# C64_Promenade.net
KiCad netlist of a schematic drawn in EAGLE
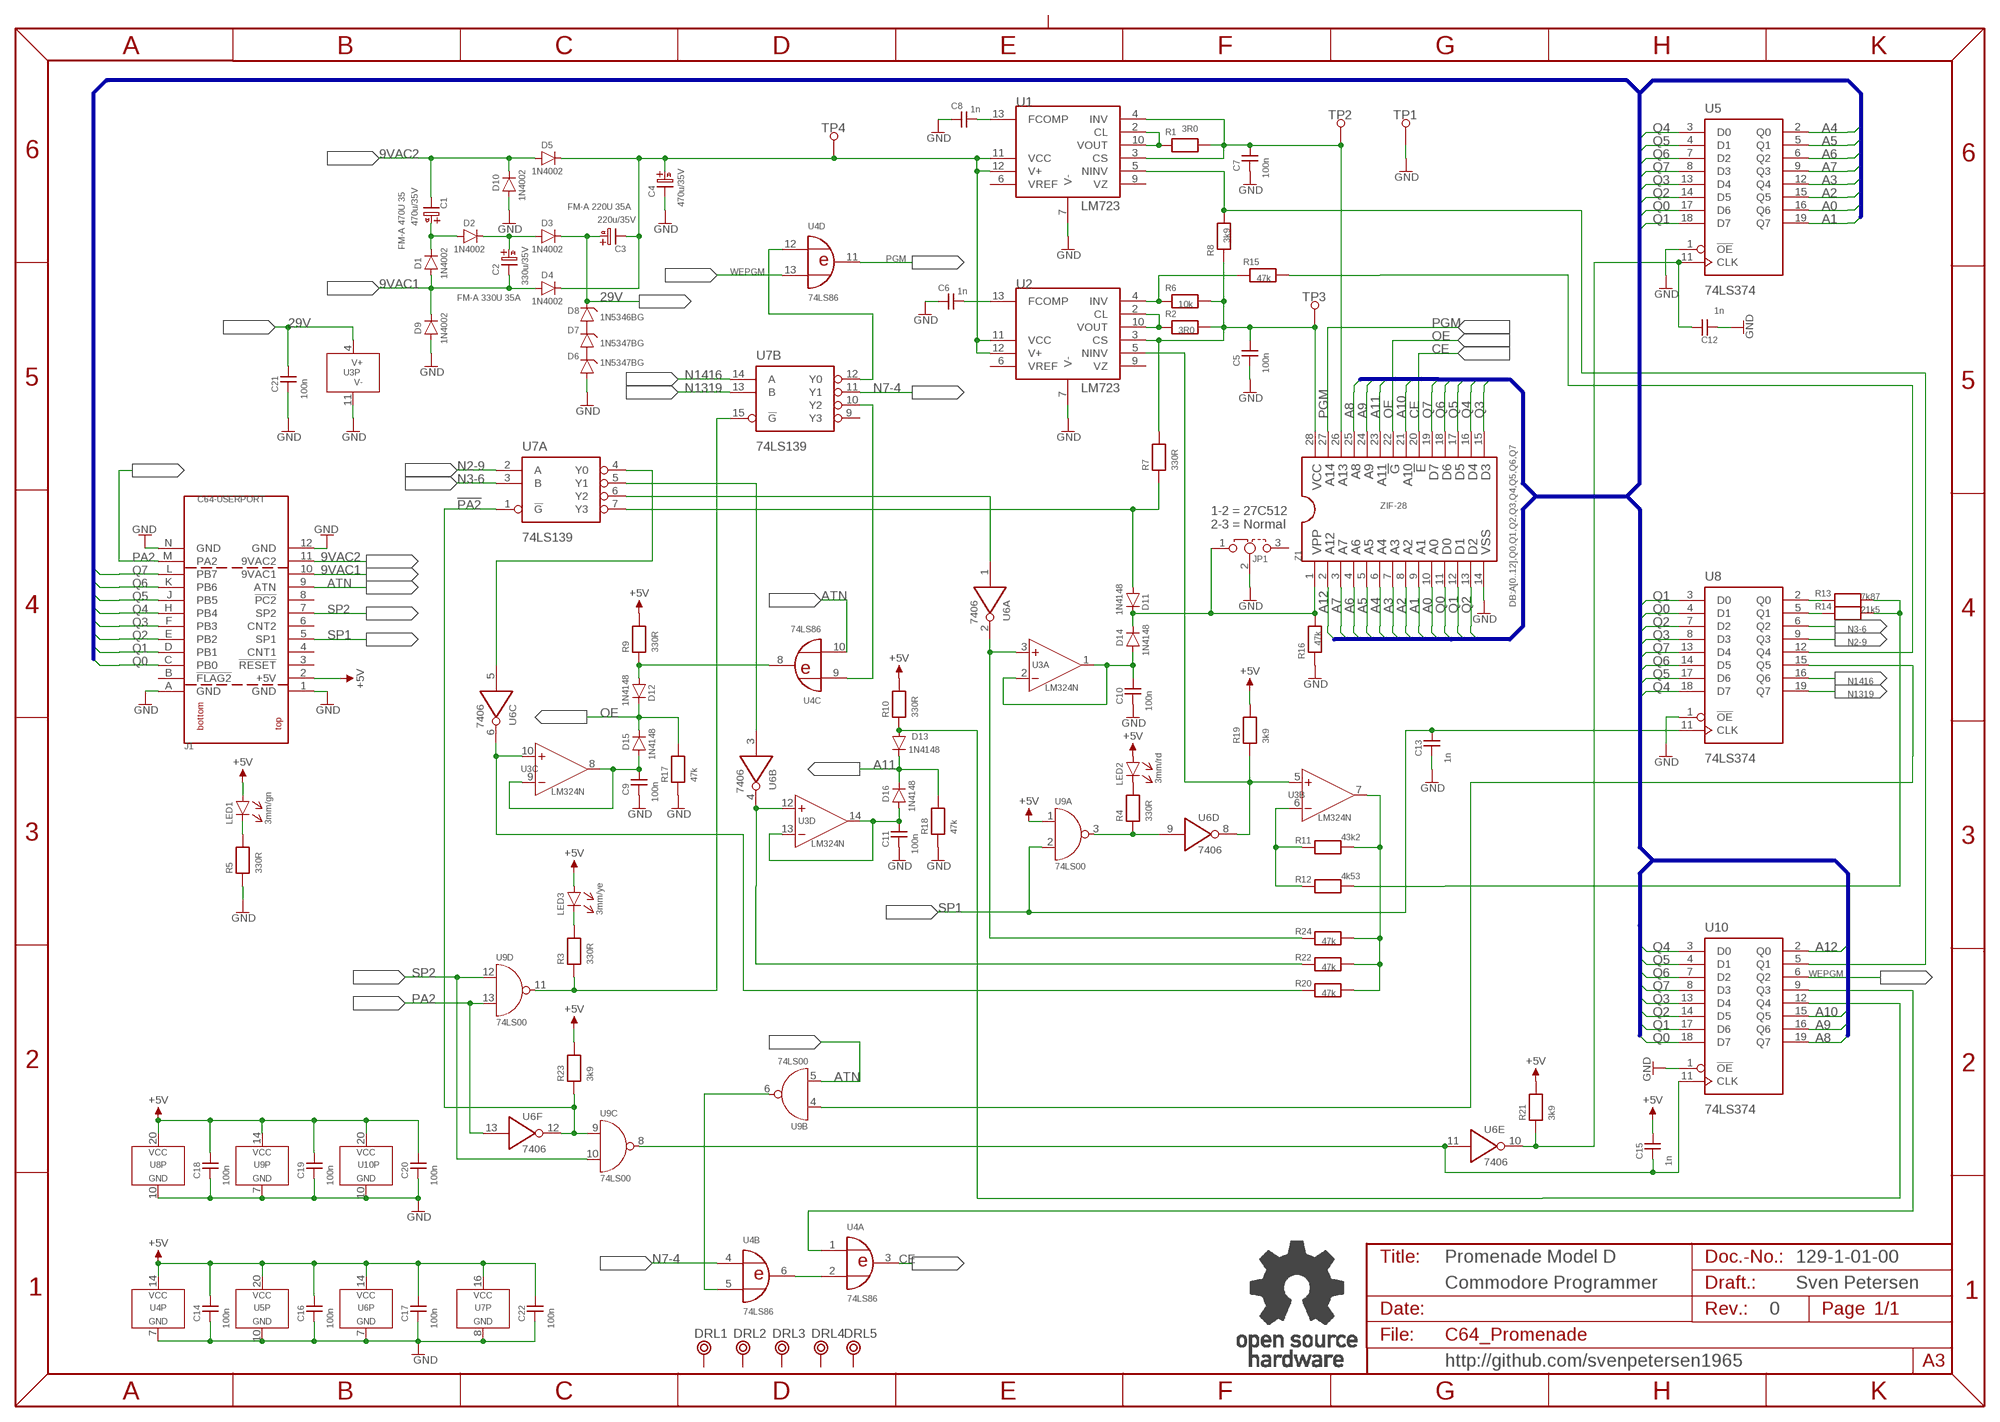
[diagram p0: schematic, sheet 1]

(export (version "E")
  (design (tool "Eeschema 10.0.6"))
  (components
    (comp (ref "C1")
      (value "470u/35V")
      (footprint "eagle-import:C10_5,0")
      (libsource (lib "eagle-import") (part "C10/5,0"))
    )
    (comp (ref "C2")
      (value "330u/35V")
      (footprint "eagle-import:C10_5,0")
      (libsource (lib "eagle-import") (part "C10/5,0"))
    )
    (comp (ref "C3")
      (value "220u/35V")
      (footprint "eagle-import:C10_5,0")
      (libsource (lib "eagle-import") (part "C10/5,0"))
    )
    (comp (ref "C4")
      (value "470u/35V")
      (footprint "eagle-import:C10_5,0")
      (libsource (lib "eagle-import") (part "C10/5,0"))
    )
    (comp (ref "C5")
      (value "100n")
      (footprint "eagle-import:C-2,5")
      (libsource (lib "eagle-import") (part "CAP01"))
    )
    (comp (ref "C6")
      (value "1n")
      (footprint "eagle-import:C-2,5")
      (libsource (lib "eagle-import") (part "CAP01"))
    )
    (comp (ref "C7")
      (value "100n")
      (footprint "eagle-import:C-2,5")
      (libsource (lib "eagle-import") (part "CAP01"))
    )
    (comp (ref "C8")
      (value "1n")
      (footprint "eagle-import:C-2,5")
      (libsource (lib "eagle-import") (part "CAP01"))
    )
    (comp (ref "C9")
      (value "100n")
      (footprint "eagle-import:C-2,5")
      (libsource (lib "eagle-import") (part "CAP01"))
    )
    (comp (ref "C10")
      (value "100n")
      (footprint "eagle-import:C-2,5")
      (libsource (lib "eagle-import") (part "CAP01"))
    )
    (comp (ref "C11")
      (value "100n")
      (footprint "eagle-import:C-2,5")
      (libsource (lib "eagle-import") (part "CAP01"))
    )
    (comp (ref "C12")
      (value "1n")
      (footprint "eagle-import:C-2,5")
      (libsource (lib "eagle-import") (part "CAP01"))
    )
    (comp (ref "C13")
      (value "1n")
      (footprint "eagle-import:C-2,5")
      (libsource (lib "eagle-import") (part "CAP01"))
    )
    (comp (ref "C14")
      (value "100n")
      (footprint "eagle-import:C-2,5")
      (libsource (lib "eagle-import") (part "CAP01"))
    )
    (comp (ref "C15")
      (value "1n")
      (footprint "eagle-import:C-2,5")
      (libsource (lib "eagle-import") (part "CAP01"))
    )
    (comp (ref "C16")
      (value "100n")
      (footprint "eagle-import:C-2,5")
      (libsource (lib "eagle-import") (part "CAP01"))
    )
    (comp (ref "C17")
      (value "100n")
      (footprint "eagle-import:C-2,5")
      (libsource (lib "eagle-import") (part "CAP01"))
    )
    (comp (ref "C18")
      (value "100n")
      (footprint "eagle-import:C-2,5")
      (libsource (lib "eagle-import") (part "CAP01"))
    )
    (comp (ref "C19")
      (value "100n")
      (footprint "eagle-import:C-2,5")
      (libsource (lib "eagle-import") (part "CAP01"))
    )
    (comp (ref "C20")
      (value "100n")
      (footprint "eagle-import:C-2,5")
      (libsource (lib "eagle-import") (part "CAP01"))
    )
    (comp (ref "C21")
      (value "100n")
      (footprint "eagle-import:C-2,5")
      (libsource (lib "eagle-import") (part "CAP01"))
    )
    (comp (ref "C22")
      (value "100n")
      (footprint "eagle-import:C-2,5")
      (libsource (lib "eagle-import") (part "CAP01"))
    )
    (comp (ref "D1")
      (value "1N4002")
      (footprint "eagle-import:DO-41")
      (libsource (lib "eagle-import") (part "1N4002"))
    )
    (comp (ref "D2")
      (value "1N4002")
      (footprint "eagle-import:DO-41")
      (libsource (lib "eagle-import") (part "1N4002"))
    )
    (comp (ref "D3")
      (value "1N4002")
      (footprint "eagle-import:DO-41")
      (libsource (lib "eagle-import") (part "1N4002"))
    )
    (comp (ref "D4")
      (value "1N4002")
      (footprint "eagle-import:DO-41")
      (libsource (lib "eagle-import") (part "1N4002"))
    )
    (comp (ref "D5")
      (value "1N4002")
      (footprint "eagle-import:DO-41")
      (libsource (lib "eagle-import") (part "1N4002"))
    )
    (comp (ref "D6")
      (value "1N5347BG")
      (footprint "eagle-import:017AA")
      (libsource (lib "eagle-import") (part "1N5347BG"))
    )
    (comp (ref "D7")
      (value "1N5347BG")
      (footprint "eagle-import:017AA")
      (libsource (lib "eagle-import") (part "1N5347BG"))
    )
    (comp (ref "D8")
      (value "1N5346BG")
      (footprint "eagle-import:017AA")
      (libsource (lib "eagle-import") (part "1N5346BG"))
    )
    (comp (ref "D9")
      (value "1N4002")
      (footprint "eagle-import:DO-41")
      (libsource (lib "eagle-import") (part "1N4002"))
    )
    (comp (ref "D10")
      (value "1N4002")
      (footprint "eagle-import:DO-41")
      (libsource (lib "eagle-import") (part "1N4002"))
    )
    (comp (ref "D11")
      (value "1N4148")
      (footprint "eagle-import:DO-35")
      (libsource (lib "eagle-import") (part "1N4148"))
    )
    (comp (ref "D12")
      (value "1N4148")
      (footprint "eagle-import:DO-35")
      (libsource (lib "eagle-import") (part "1N4148"))
    )
    (comp (ref "D13")
      (value "1N4148")
      (footprint "eagle-import:DO-35")
      (libsource (lib "eagle-import") (part "1N4148"))
    )
    (comp (ref "D14")
      (value "1N4148")
      (footprint "eagle-import:DO-35")
      (libsource (lib "eagle-import") (part "1N4148"))
    )
    (comp (ref "D15")
      (value "1N4148")
      (footprint "eagle-import:DO-35")
      (libsource (lib "eagle-import") (part "1N4148"))
    )
    (comp (ref "D16")
      (value "1N4148")
      (footprint "eagle-import:DO-35")
      (libsource (lib "eagle-import") (part "1N4148"))
    )
    (comp (ref "DRL1")
      (value "BOHR3,5")
      (footprint "eagle-import:BOHR3,5")
      (libsource (lib "eagle-import") (part "BOHR3,5"))
    )
    (comp (ref "DRL2")
      (value "BOHR3,5")
      (footprint "eagle-import:BOHR3,5")
      (libsource (lib "eagle-import") (part "BOHR3,5"))
    )
    (comp (ref "DRL3")
      (value "BOHR3,5")
      (footprint "eagle-import:BOHR3,5")
      (libsource (lib "eagle-import") (part "BOHR3,5"))
    )
    (comp (ref "DRL4")
      (value "BOHR3,5")
      (footprint "eagle-import:BOHR3,5")
      (libsource (lib "eagle-import") (part "BOHR3,5"))
    )
    (comp (ref "DRL5")
      (value "BOHR3,5")
      (footprint "eagle-import:BOHR3,5")
      (libsource (lib "eagle-import") (part "BOHR3,5"))
    )
    (comp (ref "J1")
      (value "C64-USERPORT")
      (footprint "eagle-import:USERPORT")
      (libsource (lib "eagle-import") (part "C64-USERPORT"))
    )
    (comp (ref "JP1")
      (value "DJUMPER")
      (footprint "eagle-import:1X03")
      (libsource (lib "eagle-import") (part "DJUMPER"))
    )
    (comp (ref "LED1")
      (value "3mm/gn")
      (footprint "eagle-import:3MM")
      (libsource (lib "eagle-import") (part "3MM"))
    )
    (comp (ref "LED2")
      (value "3mm/rd")
      (footprint "eagle-import:3MM")
      (libsource (lib "eagle-import") (part "3MM"))
    )
    (comp (ref "LED3")
      (value "3mm/ye")
      (footprint "eagle-import:3MM")
      (libsource (lib "eagle-import") (part "3MM"))
    )
    (comp (ref "R1")
      (value "3R0")
      (footprint "eagle-import:R-10")
      (libsource (lib "eagle-import") (part "RES04"))
    )
    (comp (ref "R2")
      (value "3R0")
      (footprint "eagle-import:R-10")
      (libsource (lib "eagle-import") (part "RES04"))
    )
    (comp (ref "R3")
      (value "330R")
      (footprint "eagle-import:R-10")
      (libsource (lib "eagle-import") (part "RES04"))
    )
    (comp (ref "R4")
      (value "330R")
      (footprint "eagle-import:R-10")
      (libsource (lib "eagle-import") (part "RES04"))
    )
    (comp (ref "R5")
      (value "330R")
      (footprint "eagle-import:R-10")
      (libsource (lib "eagle-import") (part "RES04"))
    )
    (comp (ref "R6")
      (value "10k")
      (footprint "eagle-import:R-10")
      (libsource (lib "eagle-import") (part "RES04"))
    )
    (comp (ref "R7")
      (value "330R")
      (footprint "eagle-import:R-10")
      (libsource (lib "eagle-import") (part "RES04"))
    )
    (comp (ref "R8")
      (value "3k9")
      (footprint "eagle-import:R-10")
      (libsource (lib "eagle-import") (part "RES04"))
    )
    (comp (ref "R9")
      (value "330R")
      (footprint "eagle-import:R-10")
      (libsource (lib "eagle-import") (part "RES04"))
    )
    (comp (ref "R10")
      (value "330R")
      (footprint "eagle-import:R-10")
      (libsource (lib "eagle-import") (part "RES04"))
    )
    (comp (ref "R11")
      (value "43k2")
      (footprint "eagle-import:R-10")
      (libsource (lib "eagle-import") (part "RES04"))
    )
    (comp (ref "R12")
      (value "4k53")
      (footprint "eagle-import:R-10")
      (libsource (lib "eagle-import") (part "RES04"))
    )
    (comp (ref "R13")
      (value "7k87")
      (footprint "eagle-import:R-10")
      (libsource (lib "eagle-import") (part "RES04"))
    )
    (comp (ref "R14")
      (value "21k5")
      (footprint "eagle-import:R-10")
      (libsource (lib "eagle-import") (part "RES04"))
    )
    (comp (ref "R15")
      (value "47k")
      (footprint "eagle-import:R-10")
      (libsource (lib "eagle-import") (part "RES04"))
    )
    (comp (ref "R16")
      (value "47k")
      (footprint "eagle-import:R-10")
      (libsource (lib "eagle-import") (part "RES04"))
    )
    (comp (ref "R17")
      (value "47k")
      (footprint "eagle-import:R-10")
      (libsource (lib "eagle-import") (part "RES04"))
    )
    (comp (ref "R18")
      (value "47k")
      (footprint "eagle-import:R-10")
      (libsource (lib "eagle-import") (part "RES04"))
    )
    (comp (ref "R19")
      (value "3k9")
      (footprint "eagle-import:R-10")
      (libsource (lib "eagle-import") (part "RES04"))
    )
    (comp (ref "R20")
      (value "47k")
      (footprint "eagle-import:R-10")
      (libsource (lib "eagle-import") (part "RES04"))
    )
    (comp (ref "R21")
      (value "3k9")
      (footprint "eagle-import:R-10")
      (libsource (lib "eagle-import") (part "RES04"))
    )
    (comp (ref "R22")
      (value "47k")
      (footprint "eagle-import:R-10")
      (libsource (lib "eagle-import") (part "RES04"))
    )
    (comp (ref "R23")
      (value "3k9")
      (footprint "eagle-import:R-10")
      (libsource (lib "eagle-import") (part "RES04"))
    )
    (comp (ref "R24")
      (value "47k")
      (footprint "eagle-import:R-10")
      (libsource (lib "eagle-import") (part "RES04"))
    )
    (comp (ref "TP1")
      (value "1,3/2,0")
      (footprint "eagle-import:1,3_2,0")
      (libsource (lib "eagle-import") (part "1,3/2,0"))
    )
    (comp (ref "TP2")
      (value "1,3/2,0")
      (footprint "eagle-import:1,3_2,0")
      (libsource (lib "eagle-import") (part "1,3/2,0"))
    )
    (comp (ref "TP3")
      (value "1,3/2,0")
      (footprint "eagle-import:1,3_2,0")
      (libsource (lib "eagle-import") (part "1,3/2,0"))
    )
    (comp (ref "TP4")
      (value "1,3/2,0")
      (footprint "eagle-import:1,3_2,0")
      (libsource (lib "eagle-import") (part "1,3/2,0"))
    )
    (comp (ref "U$80")
      (value "OPEN_SOURCE_HW")
      (footprint "eagle-import:OPENHW")
      (libsource (lib "eagle-import") (part "OPEN_SOURCE_HW"))
    )
    (comp (ref "U1")
      (value "LM723")
      (footprint "eagle-import:DIL-14")
      (libsource (lib "eagle-import") (part "LM723"))
    )
    (comp (ref "U2")
      (value "LM723")
      (footprint "eagle-import:DIL-14")
      (libsource (lib "eagle-import") (part "LM723"))
    )
    (comp (ref "U3")
      (value "LM324N")
      (footprint "eagle-import:DIL-14")
      (libsource (lib "eagle-import") (part "LM324N"))
    )
    (comp (ref "U4")
      (value "74LS86")
      (footprint "eagle-import:DIL-14")
      (libsource (lib "eagle-import") (part "7486N"))
    )
    (comp (ref "U5")
      (value "74LS374")
      (footprint "eagle-import:DIL-20")
      (libsource (lib "eagle-import") (part "74374N"))
    )
    (comp (ref "U6")
      (value "7406")
      (footprint "eagle-import:DIL-14")
      (libsource (lib "eagle-import") (part "7406N"))
    )
    (comp (ref "U7")
      (value "74LS139")
      (footprint "eagle-import:DIL-16")
      (libsource (lib "eagle-import") (part "74139N"))
    )
    (comp (ref "U8")
      (value "74LS374")
      (footprint "eagle-import:DIL-20")
      (libsource (lib "eagle-import") (part "74374N"))
    )
    (comp (ref "U9")
      (value "74LS00")
      (footprint "eagle-import:DIL-14")
      (libsource (lib "eagle-import") (part "7400DIP"))
    )
    (comp (ref "U10")
      (value "74LS374")
      (footprint "eagle-import:DIL-20")
      (libsource (lib "eagle-import") (part "74374N"))
    )
    (comp (ref "Z1")
      (value "ZIF-28")
      (footprint "eagle-import:ZIF28")
      (libsource (lib "eagle-import") (part "ZIF-28"))
    )
  )
  (nets
    (net (code "1") (name "+5V") (class "Default")
      (node (ref "C14") (pin "2") (pinfunction "2_2") (pintype "passive"))
      (node (ref "C15") (pin "2") (pinfunction "2_2") (pintype "passive"))
      (node (ref "C16") (pin "2") (pinfunction "2_2") (pintype "passive"))
      (node (ref "C17") (pin "2") (pinfunction "2_2") (pintype "passive"))
      (node (ref "C18") (pin "2") (pinfunction "2_2") (pintype "passive"))
      (node (ref "C19") (pin "2") (pinfunction "2_2") (pintype "passive"))
      (node (ref "C20") (pin "2") (pinfunction "2_2") (pintype "passive"))
      (node (ref "C22") (pin "2") (pinfunction "2_2") (pintype "passive"))
      (node (ref "J1") (pin "2") (pinfunction "+5V_2") (pintype "power_in"))
      (node (ref "LED1") (pin "A") (pinfunction "A_A") (pintype "bidirectional"))
      (node (ref "LED2") (pin "A") (pinfunction "A_A") (pintype "bidirectional"))
      (node (ref "LED3") (pin "A") (pinfunction "A_A") (pintype "bidirectional"))
      (node (ref "R10") (pin "2") (pinfunction "2_2") (pintype "passive"))
      (node (ref "R19") (pin "2") (pinfunction "2_2") (pintype "passive"))
      (node (ref "R21") (pin "2") (pinfunction "2_2") (pintype "passive"))
      (node (ref "R23") (pin "2") (pinfunction "2_2") (pintype "passive"))
      (node (ref "R9") (pin "2") (pinfunction "2_2") (pintype "passive"))
      (node (ref "U10") (pin "20") (pinfunction "VCC_20") (pintype "bidirectional"))
      (node (ref "U4") (pin "14") (pinfunction "VCC_14") (pintype "bidirectional"))
      (node (ref "U5") (pin "20") (pinfunction "VCC_20") (pintype "bidirectional"))
      (node (ref "U6") (pin "14") (pinfunction "VCC_14") (pintype "bidirectional"))
      (node (ref "U7") (pin "16") (pinfunction "VCC_16") (pintype "bidirectional"))
      (node (ref "U8") (pin "20") (pinfunction "VCC_20") (pintype "bidirectional"))
      (node (ref "U9") (pin "1") (pinfunction "I0_1") (pintype "input"))
      (node (ref "U9") (pin "14") (pinfunction "VCC_14") (pintype "bidirectional"))
    )
    (net (code "2") (name "/9VAC1") (class "Default")
      (node (ref "C2") (pin "-") (pinfunction "-_-") (pintype "passive"))
      (node (ref "D1") (pin "A") (pinfunction "A_A") (pintype "passive"))
      (node (ref "D4") (pin "A") (pinfunction "A_A") (pintype "passive"))
      (node (ref "D9") (pin "K") (pinfunction "K_K") (pintype "passive"))
      (node (ref "J1") (pin "10") (pinfunction "9VAC1_10") (pintype "power_in"))
    )
    (net (code "3") (name "/9VAC2") (class "Default")
      (node (ref "C1") (pin "-") (pinfunction "-_-") (pintype "passive"))
      (node (ref "D10") (pin "K") (pinfunction "K_K") (pintype "passive"))
      (node (ref "D5") (pin "A") (pinfunction "A_A") (pintype "passive"))
      (node (ref "J1") (pin "11") (pinfunction "9VAC2_11") (pintype "power_in"))
    )
    (net (code "4") (name "/29V") (class "Default")
      (node (ref "C21") (pin "2") (pinfunction "2_2") (pintype "passive"))
      (node (ref "C3") (pin "+") (pinfunction "+_+") (pintype "passive"))
      (node (ref "D3") (pin "K") (pinfunction "K_K") (pintype "passive"))
      (node (ref "D8") (pin "K") (pinfunction "K_K") (pintype "passive"))
      (node (ref "U3") (pin "4") (pinfunction "V+_4") (pintype "power_in"))
    )
    (net (code "5") (name "/A0") (class "Default")
      (node (ref "U5") (pin "16") (pinfunction "Q6_16") (pintype "tri_state"))
      (node (ref "Z1") (pin "10") (pinfunction "10_10") (pintype "bidirectional"))
    )
    (net (code "6") (name "/A1") (class "Default")
      (node (ref "U5") (pin "19") (pinfunction "Q7_19") (pintype "tri_state"))
      (node (ref "Z1") (pin "9") (pinfunction "9_9") (pintype "bidirectional"))
    )
    (net (code "7") (name "/A2") (class "Default")
      (node (ref "U5") (pin "15") (pinfunction "Q5_15") (pintype "tri_state"))
      (node (ref "Z1") (pin "8") (pinfunction "8_8") (pintype "bidirectional"))
    )
    (net (code "8") (name "/A3") (class "Default")
      (node (ref "U5") (pin "12") (pinfunction "Q4_12") (pintype "tri_state"))
      (node (ref "Z1") (pin "7") (pinfunction "7_7") (pintype "bidirectional"))
    )
    (net (code "9") (name "/A4") (class "Default")
      (node (ref "U5") (pin "2") (pinfunction "Q0_2") (pintype "tri_state"))
      (node (ref "Z1") (pin "6") (pinfunction "6_6") (pintype "bidirectional"))
    )
    (net (code "10") (name "/A5") (class "Default")
      (node (ref "U5") (pin "5") (pinfunction "Q1_5") (pintype "tri_state"))
      (node (ref "Z1") (pin "5") (pinfunction "5_5") (pintype "bidirectional"))
    )
    (net (code "11") (name "/A6") (class "Default")
      (node (ref "U5") (pin "6") (pinfunction "Q2_6") (pintype "tri_state"))
      (node (ref "Z1") (pin "4") (pinfunction "4_4") (pintype "bidirectional"))
    )
    (net (code "12") (name "/A7") (class "Default")
      (node (ref "U5") (pin "9") (pinfunction "Q3_9") (pintype "tri_state"))
      (node (ref "Z1") (pin "3") (pinfunction "3_3") (pintype "bidirectional"))
    )
    (net (code "13") (name "/A8") (class "Default")
      (node (ref "U10") (pin "19") (pinfunction "Q7_19") (pintype "tri_state"))
      (node (ref "Z1") (pin "25") (pinfunction "25_25") (pintype "bidirectional"))
    )
    (net (code "14") (name "/A9") (class "Default")
      (node (ref "U10") (pin "16") (pinfunction "Q6_16") (pintype "tri_state"))
      (node (ref "Z1") (pin "24") (pinfunction "24_24") (pintype "bidirectional"))
    )
    (net (code "15") (name "/A10") (class "Default")
      (node (ref "U10") (pin "15") (pinfunction "Q5_15") (pintype "tri_state"))
      (node (ref "Z1") (pin "21") (pinfunction "21_21") (pintype "bidirectional"))
    )
    (net (code "16") (name "/A11") (class "Default")
      (node (ref "D13") (pin "K") (pinfunction "K_K") (pintype "passive"))
      (node (ref "D16") (pin "K") (pinfunction "K_K") (pintype "passive"))
      (node (ref "R18") (pin "2") (pinfunction "2_2") (pintype "passive"))
      (node (ref "Z1") (pin "23") (pinfunction "23_23") (pintype "bidirectional"))
    )
    (net (code "17") (name "/A12") (class "Default")
      (node (ref "U10") (pin "2") (pinfunction "Q0_2") (pintype "tri_state"))
      (node (ref "Z1") (pin "2") (pinfunction "2_2") (pintype "bidirectional"))
    )
    (net (code "18") (name "/ATN") (class "Default")
      (node (ref "J1") (pin "9") (pinfunction "ATN_9") (pintype "bidirectional"))
      (node (ref "U4") (pin "10") (pinfunction "I1_10") (pintype "input"))
      (node (ref "U9") (pin "5") (pinfunction "I1_5") (pintype "input"))
    )
    (net (code "19") (name "/CE") (class "Default")
      (node (ref "U4") (pin "3") (pinfunction "O_3") (pintype "output"))
      (node (ref "Z1") (pin "20") (pinfunction "20_20") (pintype "bidirectional"))
    )
    (net (code "20") (name "/N2-9") (class "Default")
      (node (ref "U7") (pin "2") (pinfunction "A_2") (pintype "input"))
      (node (ref "U8") (pin "9") (pinfunction "Q3_9") (pintype "tri_state"))
    )
    (net (code "21") (name "/N3-6") (class "Default")
      (node (ref "U7") (pin "3") (pinfunction "B_3") (pintype "input"))
      (node (ref "U8") (pin "6") (pinfunction "Q2_6") (pintype "tri_state"))
    )
    (net (code "22") (name "/N7-4") (class "Default")
      (node (ref "U4") (pin "4") (pinfunction "I0_4") (pintype "input"))
      (node (ref "U7") (pin "11") (pinfunction "Y1_11") (pintype "output"))
    )
    (net (code "23") (name "/N1319") (class "Default")
      (node (ref "U7") (pin "13") (pinfunction "B_13") (pintype "input"))
      (node (ref "U8") (pin "19") (pinfunction "Q7_19") (pintype "tri_state"))
    )
    (net (code "24") (name "/N1416") (class "Default")
      (node (ref "U7") (pin "14") (pinfunction "A_14") (pintype "input"))
      (node (ref "U8") (pin "16") (pinfunction "Q6_16") (pintype "tri_state"))
    )
    (net (code "25") (name "/OE") (class "Default")
      (node (ref "D12") (pin "K") (pinfunction "K_K") (pintype "passive"))
      (node (ref "D15") (pin "K") (pinfunction "K_K") (pintype "passive"))
      (node (ref "R17") (pin "2") (pinfunction "2_2") (pintype "passive"))
      (node (ref "Z1") (pin "22") (pinfunction "22_22") (pintype "bidirectional"))
    )
    (net (code "26") (name "/PA2") (class "Default")
      (node (ref "J1") (pin "M") (pinfunction "PA2_M") (pintype "bidirectional"))
      (node (ref "U6") (pin "13") (pinfunction "I_13") (pintype "input"))
      (node (ref "U9") (pin "13") (pinfunction "I1_13") (pintype "input"))
    )
    (net (code "27") (name "/PGM") (class "Default")
      (node (ref "U4") (pin "11") (pinfunction "O_11") (pintype "output"))
      (node (ref "Z1") (pin "27") (pinfunction "27_27") (pintype "bidirectional"))
    )
    (net (code "28") (name "/Q0") (class "Default")
      (node (ref "J1") (pin "C") (pinfunction "PB0_C") (pintype "bidirectional"))
      (node (ref "U10") (pin "18") (pinfunction "D7_18") (pintype "input"))
      (node (ref "U5") (pin "17") (pinfunction "D6_17") (pintype "input"))
      (node (ref "U8") (pin "4") (pinfunction "D1_4") (pintype "input"))
      (node (ref "Z1") (pin "11") (pinfunction "11_11") (pintype "bidirectional"))
    )
    (net (code "29") (name "/Q1") (class "Default")
      (node (ref "J1") (pin "D") (pinfunction "PB1_D") (pintype "bidirectional"))
      (node (ref "U10") (pin "17") (pinfunction "D6_17") (pintype "input"))
      (node (ref "U5") (pin "18") (pinfunction "D7_18") (pintype "input"))
      (node (ref "U8") (pin "3") (pinfunction "D0_3") (pintype "input"))
      (node (ref "Z1") (pin "12") (pinfunction "12_12") (pintype "bidirectional"))
    )
    (net (code "30") (name "/Q2") (class "Default")
      (node (ref "J1") (pin "E") (pinfunction "PB2_E") (pintype "bidirectional"))
      (node (ref "U10") (pin "14") (pinfunction "D5_14") (pintype "input"))
      (node (ref "U5") (pin "14") (pinfunction "D5_14") (pintype "input"))
      (node (ref "U8") (pin "7") (pinfunction "D2_7") (pintype "input"))
      (node (ref "Z1") (pin "13") (pinfunction "13_13") (pintype "bidirectional"))
    )
    (net (code "31") (name "/Q3") (class "Default")
      (node (ref "J1") (pin "F") (pinfunction "PB3_F") (pintype "bidirectional"))
      (node (ref "U10") (pin "13") (pinfunction "D4_13") (pintype "input"))
      (node (ref "U5") (pin "13") (pinfunction "D4_13") (pintype "input"))
      (node (ref "U8") (pin "8") (pinfunction "D3_8") (pintype "input"))
      (node (ref "Z1") (pin "15") (pinfunction "15_15") (pintype "bidirectional"))
    )
    (net (code "32") (name "/Q4") (class "Default")
      (node (ref "J1") (pin "H") (pinfunction "PB4_H") (pintype "bidirectional"))
      (node (ref "U10") (pin "3") (pinfunction "D0_3") (pintype "input"))
      (node (ref "U5") (pin "3") (pinfunction "D0_3") (pintype "input"))
      (node (ref "U8") (pin "18") (pinfunction "D7_18") (pintype "input"))
      (node (ref "Z1") (pin "16") (pinfunction "16_16") (pintype "bidirectional"))
    )
    (net (code "33") (name "/Q5") (class "Default")
      (node (ref "J1") (pin "J") (pinfunction "PB5_J") (pintype "bidirectional"))
      (node (ref "U10") (pin "4") (pinfunction "D1_4") (pintype "input"))
      (node (ref "U5") (pin "4") (pinfunction "D1_4") (pintype "input"))
      (node (ref "U8") (pin "17") (pinfunction "D6_17") (pintype "input"))
      (node (ref "Z1") (pin "17") (pinfunction "17_17") (pintype "bidirectional"))
    )
    (net (code "34") (name "/Q6") (class "Default")
      (node (ref "J1") (pin "K") (pinfunction "PB6_K") (pintype "bidirectional"))
      (node (ref "U10") (pin "7") (pinfunction "D2_7") (pintype "input"))
      (node (ref "U5") (pin "7") (pinfunction "D2_7") (pintype "input"))
      (node (ref "U8") (pin "14") (pinfunction "D5_14") (pintype "input"))
      (node (ref "Z1") (pin "18") (pinfunction "18_18") (pintype "bidirectional"))
    )
    (net (code "35") (name "/Q7") (class "Default")
      (node (ref "J1") (pin "L") (pinfunction "PB7_L") (pintype "bidirectional"))
      (node (ref "U10") (pin "8") (pinfunction "D3_8") (pintype "input"))
      (node (ref "U5") (pin "8") (pinfunction "D3_8") (pintype "input"))
      (node (ref "U8") (pin "13") (pinfunction "D4_13") (pintype "input"))
      (node (ref "Z1") (pin "19") (pinfunction "19_19") (pintype "bidirectional"))
    )
    (net (code "36") (name "/SP1") (class "Default")
      (node (ref "C13") (pin "2") (pinfunction "2_2") (pintype "passive"))
      (node (ref "J1") (pin "5") (pinfunction "SP1_5") (pintype "bidirectional"))
      (node (ref "U8") (pin "11") (pinfunction "CLK_11") (pintype "input"))
      (node (ref "U9") (pin "2") (pinfunction "I1_2") (pintype "input"))
    )
    (net (code "37") (name "/SP2") (class "Default")
      (node (ref "J1") (pin "7") (pinfunction "SP2_7") (pintype "bidirectional"))
      (node (ref "U9") (pin "10") (pinfunction "I1_10") (pintype "input"))
      (node (ref "U9") (pin "12") (pinfunction "I0_12") (pintype "input"))
    )
    (net (code "38") (name "/WEPGM") (class "Default")
      (node (ref "U10") (pin "6") (pinfunction "Q2_6") (pintype "tri_state"))
      (node (ref "U4") (pin "13") (pinfunction "I1_13") (pintype "input"))
    )
    (net (code "40") (name "/~{PA2}") (class "Default")
      (node (ref "R23") (pin "1") (pinfunction "1_1") (pintype "passive"))
      (node (ref "U6") (pin "12") (pinfunction "O_12") (pintype "open_collector"))
      (node (ref "U7") (pin "1") (pinfunction "~{G}_1") (pintype "input"))
      (node (ref "U9") (pin "9") (pinfunction "I0_9") (pintype "input"))
    )
    (net (code "41") (name "GND") (class "Default")
      (node (ref "C10") (pin "1") (pinfunction "1_1") (pintype "passive"))
      (node (ref "C11") (pin "1") (pinfunction "1_1") (pintype "passive"))
      (node (ref "C12") (pin "1") (pinfunction "1_1") (pintype "passive"))
      (node (ref "C13") (pin "1") (pinfunction "1_1") (pintype "passive"))
      (node (ref "C14") (pin "1") (pinfunction "1_1") (pintype "passive"))
      (node (ref "C16") (pin "1") (pinfunction "1_1") (pintype "passive"))
      (node (ref "C17") (pin "1") (pinfunction "1_1") (pintype "passive"))
      (node (ref "C18") (pin "1") (pinfunction "1_1") (pintype "passive"))
      (node (ref "C19") (pin "1") (pinfunction "1_1") (pintype "passive"))
      (node (ref "C20") (pin "1") (pinfunction "1_1") (pintype "passive"))
      (node (ref "C21") (pin "1") (pinfunction "1_1") (pintype "passive"))
      (node (ref "C22") (pin "1") (pinfunction "1_1") (pintype "passive"))
      (node (ref "C4") (pin "-") (pinfunction "-_-") (pintype "passive"))
      (node (ref "C5") (pin "1") (pinfunction "1_1") (pintype "passive"))
      (node (ref "C6") (pin "1") (pinfunction "1_1") (pintype "passive"))
      (node (ref "C7") (pin "1") (pinfunction "1_1") (pintype "passive"))
      (node (ref "C8") (pin "1") (pinfunction "1_1") (pintype "passive"))
      (node (ref "C9") (pin "1") (pinfunction "1_1") (pintype "passive"))
      (node (ref "D10") (pin "A") (pinfunction "A_A") (pintype "passive"))
      (node (ref "D6") (pin "A") (pinfunction "A_A") (pintype "passive"))
      (node (ref "D9") (pin "A") (pinfunction "A_A") (pintype "passive"))
      (node (ref "J1") (pin "1") (pinfunction "GND_1") (pintype "power_in"))
      (node (ref "J1") (pin "12") (pinfunction "GND_12") (pintype "power_in"))
      (node (ref "J1") (pin "A") (pinfunction "GND_A") (pintype "power_in"))
      (node (ref "J1") (pin "N") (pinfunction "GND_N") (pintype "power_in"))
      (node (ref "JP1") (pin "2") (pinfunction "2_2") (pintype "bidirectional"))
      (node (ref "R16") (pin "2") (pinfunction "2_2") (pintype "passive"))
      (node (ref "R17") (pin "1") (pinfunction "1_1") (pintype "passive"))
      (node (ref "R18") (pin "1") (pinfunction "1_1") (pintype "passive"))
      (node (ref "R5") (pin "1") (pinfunction "1_1") (pintype "passive"))
      (node (ref "TP1") (pin "1") (pinfunction "1_1") (pintype "passive"))
      (node (ref "U1") (pin "7") (pinfunction "V-_7") (pintype "power_in"))
      (node (ref "U10") (pin "1") (pinfunction "~{OE}_1") (pintype "input"))
      (node (ref "U10") (pin "10") (pinfunction "GND_10") (pintype "bidirectional"))
      (node (ref "U2") (pin "7") (pinfunction "V-_7") (pintype "power_in"))
      (node (ref "U3") (pin "11") (pinfunction "V-_11") (pintype "power_in"))
      (node (ref "U4") (pin "7") (pinfunction "GND_7") (pintype "bidirectional"))
      (node (ref "U5") (pin "1") (pinfunction "~{OE}_1") (pintype "input"))
      (node (ref "U5") (pin "10") (pinfunction "GND_10") (pintype "bidirectional"))
      (node (ref "U6") (pin "7") (pinfunction "GND_7") (pintype "bidirectional"))
      (node (ref "U7") (pin "8") (pinfunction "GND_8") (pintype "bidirectional"))
      (node (ref "U8") (pin "1") (pinfunction "~{OE}_1") (pintype "input"))
      (node (ref "U8") (pin "10") (pinfunction "GND_10") (pintype "bidirectional"))
      (node (ref "U9") (pin "7") (pinfunction "GND_7") (pintype "bidirectional"))
      (node (ref "Z1") (pin "14") (pinfunction "14_14") (pintype "bidirectional"))
    )
    (net (code "42") (name "Net-(C1-Pad+)") (class "Default")
      (node (ref "C1") (pin "+") (pinfunction "+_+") (pintype "passive"))
      (node (ref "D1") (pin "K") (pinfunction "K_K") (pintype "passive"))
      (node (ref "D2") (pin "A") (pinfunction "A_A") (pintype "passive"))
    )
    (net (code "43") (name "Net-(C2-Pad+)") (class "Default")
      (node (ref "C2") (pin "+") (pinfunction "+_+") (pintype "passive"))
      (node (ref "D2") (pin "K") (pinfunction "K_K") (pintype "passive"))
      (node (ref "D3") (pin "A") (pinfunction "A_A") (pintype "passive"))
    )
    (net (code "44") (name "Net-(D6-PadK)") (class "Default")
      (node (ref "D6") (pin "K") (pinfunction "K_K") (pintype "passive"))
      (node (ref "D7") (pin "A") (pinfunction "A_A") (pintype "passive"))
    )
    (net (code "45") (name "Net-(D7-PadK)") (class "Default")
      (node (ref "D7") (pin "K") (pinfunction "K_K") (pintype "passive"))
      (node (ref "D8") (pin "A") (pinfunction "A_A") (pintype "passive"))
    )
    (net (code "46") (name "Net-(D11-PadK)") (class "Default")
      (node (ref "D11") (pin "K") (pinfunction "K_K") (pintype "passive"))
      (node (ref "D14") (pin "K") (pinfunction "K_K") (pintype "passive"))
      (node (ref "JP1") (pin "1") (pinfunction "1_1") (pintype "bidirectional"))
      (node (ref "R16") (pin "1") (pinfunction "1_1") (pintype "passive"))
      (node (ref "Z1") (pin "1") (pinfunction "1_1") (pintype "bidirectional"))
    )
    (net (code "47") (name "Net-(LED1-K)") (class "Default")
      (node (ref "LED1") (pin "C") (pinfunction "K_C") (pintype "bidirectional"))
      (node (ref "R5") (pin "2") (pinfunction "2_2") (pintype "passive"))
    )
    (net (code "48") (name "Net-(LED2-K)") (class "Default")
      (node (ref "LED2") (pin "C") (pinfunction "K_C") (pintype "bidirectional"))
      (node (ref "R4") (pin "2") (pinfunction "2_2") (pintype "passive"))
    )
    (net (code "49") (name "Net-(LED3-K)") (class "Default")
      (node (ref "LED3") (pin "C") (pinfunction "K_C") (pintype "bidirectional"))
      (node (ref "R3") (pin "2") (pinfunction "2_2") (pintype "passive"))
    )
    (net (code "50") (name "Net-(R12-Pad2)") (class "Default")
      (node (ref "R12") (pin "2") (pinfunction "2_2") (pintype "passive"))
      (node (ref "R13") (pin "1") (pinfunction "1_1") (pintype "passive"))
      (node (ref "R14") (pin "1") (pinfunction "1_1") (pintype "passive"))
    )
    (net (code "51") (name "Net-(U1-CL)") (class "Default")
      (node (ref "R1") (pin "2") (pinfunction "2_2") (pintype "passive"))
      (node (ref "U1") (pin "10") (pinfunction "VOUT_10") (pintype "output"))
      (node (ref "U1") (pin "2") (pinfunction "CL_2") (pintype "input"))
    )
    (net (code "52") (name "Net-(U1-CS)") (class "Default")
      (node (ref "C7") (pin "2") (pinfunction "2_2") (pintype "passive"))
      (node (ref "R1") (pin "1") (pinfunction "1_1") (pintype "passive"))
      (node (ref "TP2") (pin "1") (pinfunction "1_1") (pintype "passive"))
      (node (ref "U1") (pin "3") (pinfunction "CS_3") (pintype "passive"))
      (node (ref "U1") (pin "4") (pinfunction "INV_4") (pintype "input"))
      (node (ref "Z1") (pin "26") (pinfunction "26_26") (pintype "bidirectional"))
    )
    (net (code "53") (name "Net-(U1-FCOMP)") (class "Default")
      (node (ref "C8") (pin "2") (pinfunction "2_2") (pintype "passive"))
      (node (ref "U1") (pin "13") (pinfunction "FCOMP_13") (pintype "passive"))
    )
    (net (code "54") (name "Net-(U1-NINV)") (class "Default")
      (node (ref "R8") (pin "1") (pinfunction "1_1") (pintype "passive"))
      (node (ref "U1") (pin "5") (pinfunction "NINV_5") (pintype "input"))
      (node (ref "U10") (pin "5") (pinfunction "Q1_5") (pintype "tri_state"))
    )
    (net (code "55") (name "Net-(U1-V+)") (class "Default")
      (node (ref "C3") (pin "-") (pinfunction "-_-") (pintype "passive"))
      (node (ref "C4") (pin "+") (pinfunction "+_+") (pintype "passive"))
      (node (ref "D4") (pin "K") (pinfunction "K_K") (pintype "passive"))
      (node (ref "D5") (pin "K") (pinfunction "K_K") (pintype "passive"))
      (node (ref "TP4") (pin "1") (pinfunction "1_1") (pintype "passive"))
      (node (ref "U1") (pin "11") (pinfunction "VCC_11") (pintype "power_in"))
      (node (ref "U1") (pin "12") (pinfunction "V+_12") (pintype "power_in"))
      (node (ref "U2") (pin "11") (pinfunction "VCC_11") (pintype "power_in"))
      (node (ref "U2") (pin "12") (pinfunction "V+_12") (pintype "power_in"))
    )
    (net (code "56") (name "Net-(U2-CL)") (class "Default")
      (node (ref "R2") (pin "2") (pinfunction "2_2") (pintype "passive"))
      (node (ref "U2") (pin "10") (pinfunction "VOUT_10") (pintype "output"))
      (node (ref "U2") (pin "2") (pinfunction "CL_2") (pintype "input"))
    )
    (net (code "57") (name "Net-(U2-CS)") (class "Default")
      (node (ref "C5") (pin "2") (pinfunction "2_2") (pintype "passive"))
      (node (ref "R2") (pin "1") (pinfunction "1_1") (pintype "passive"))
      (node (ref "R6") (pin "1") (pinfunction "1_1") (pintype "passive"))
      (node (ref "R7") (pin "2") (pinfunction "2_2") (pintype "passive"))
      (node (ref "R8") (pin "2") (pinfunction "2_2") (pintype "passive"))
      (node (ref "TP3") (pin "1") (pinfunction "1_1") (pintype "passive"))
      (node (ref "U2") (pin "3") (pinfunction "CS_3") (pintype "passive"))
      (node (ref "Z1") (pin "28") (pinfunction "28_28") (pintype "bidirectional"))
    )
    (net (code "58") (name "Net-(U2-FCOMP)") (class "Default")
      (node (ref "C6") (pin "2") (pinfunction "2_2") (pintype "passive"))
      (node (ref "U2") (pin "13") (pinfunction "FCOMP_13") (pintype "passive"))
    )
    (net (code "59") (name "Net-(U2-INV)") (class "Default")
      (node (ref "R15") (pin "2") (pinfunction "2_2") (pintype "passive"))
      (node (ref "R6") (pin "2") (pinfunction "2_2") (pintype "passive"))
      (node (ref "U2") (pin "4") (pinfunction "INV_4") (pintype "input"))
    )
    (net (code "60") (name "Net-(U2-NINV)") (class "Default")
      (node (ref "R19") (pin "1") (pinfunction "1_1") (pintype "passive"))
      (node (ref "U2") (pin "5") (pinfunction "NINV_5") (pintype "input"))
      (node (ref "U3") (pin "5") (pinfunction "+_5") (pintype "input"))
      (node (ref "U6") (pin "8") (pinfunction "O_8") (pintype "open_collector"))
    )
    (net (code "61") (name "Net-(U3A-+)") (class "Default")
      (node (ref "R24") (pin "1") (pinfunction "1_1") (pintype "passive"))
      (node (ref "U3") (pin "3") (pinfunction "+_3") (pintype "input"))
      (node (ref "U6") (pin "2") (pinfunction "O_2") (pintype "open_collector"))
    )
    (net (code "62") (name "Net-(U3A--)") (class "Default")
      (node (ref "C10") (pin "2") (pinfunction "2_2") (pintype "passive"))
      (node (ref "D14") (pin "A") (pinfunction "A_A") (pintype "passive"))
      (node (ref "U3") (pin "1") (pinfunction "O_1") (pintype "output"))
      (node (ref "U3") (pin "2") (pinfunction "-_2") (pintype "input"))
    )
    (net (code "63") (name "Net-(U3B--)") (class "Default")
      (node (ref "R11") (pin "1") (pinfunction "1_1") (pintype "passive"))
      (node (ref "R12") (pin "1") (pinfunction "1_1") (pintype "passive"))
      (node (ref "U3") (pin "6") (pinfunction "-_6") (pintype "input"))
    )
    (net (code "64") (name "Net-(U3B-O)") (class "Default")
      (node (ref "R11") (pin "2") (pinfunction "2_2") (pintype "passive"))
      (node (ref "R20") (pin "2") (pinfunction "2_2") (pintype "passive"))
      (node (ref "R22") (pin "2") (pinfunction "2_2") (pintype "passive"))
      (node (ref "R24") (pin "2") (pinfunction "2_2") (pintype "passive"))
      (node (ref "U3") (pin "7") (pinfunction "O_7") (pintype "output"))
    )
    (net (code "65") (name "Net-(U3C-+)") (class "Default")
      (node (ref "R20") (pin "1") (pinfunction "1_1") (pintype "passive"))
      (node (ref "U3") (pin "10") (pinfunction "+_10") (pintype "input"))
      (node (ref "U6") (pin "6") (pinfunction "O_6") (pintype "open_collector"))
    )
    (net (code "66") (name "Net-(U3C--)") (class "Default")
      (node (ref "C9") (pin "2") (pinfunction "2_2") (pintype "passive"))
      (node (ref "D15") (pin "A") (pinfunction "A_A") (pintype "passive"))
      (node (ref "U3") (pin "8") (pinfunction "O_8") (pintype "output"))
      (node (ref "U3") (pin "9") (pinfunction "-_9") (pintype "input"))
    )
    (net (code "67") (name "Net-(U3D-+)") (class "Default")
      (node (ref "R22") (pin "1") (pinfunction "1_1") (pintype "passive"))
      (node (ref "U3") (pin "12") (pinfunction "+_12") (pintype "input"))
      (node (ref "U6") (pin "4") (pinfunction "O_4") (pintype "open_collector"))
    )
    (net (code "68") (name "Net-(U3D--)") (class "Default")
      (node (ref "C11") (pin "2") (pinfunction "2_2") (pintype "passive"))
      (node (ref "D16") (pin "A") (pinfunction "A_A") (pintype "passive"))
      (node (ref "U3") (pin "13") (pinfunction "-_13") (pintype "input"))
      (node (ref "U3") (pin "14") (pinfunction "O_14") (pintype "output"))
    )
    (net (code "69") (name "Net-(U4A-I1)") (class "Default")
      (node (ref "U4") (pin "2") (pinfunction "I1_2") (pintype "input"))
      (node (ref "U4") (pin "6") (pinfunction "O_6") (pintype "output"))
    )
    (net (code "70") (name "Net-(U4B-I1)") (class "Default")
      (node (ref "U4") (pin "5") (pinfunction "I1_5") (pintype "input"))
      (node (ref "U9") (pin "6") (pinfunction "O_6") (pintype "output"))
    )
    (net (code "71") (name "Net-(U4C-I0)") (class "Default")
      (node (ref "U4") (pin "9") (pinfunction "I0_9") (pintype "input"))
      (node (ref "U7") (pin "10") (pinfunction "Y2_10") (pintype "output"))
    )
    (net (code "72") (name "Net-(U4C-O)") (class "Default")
      (node (ref "D12") (pin "A") (pinfunction "A_A") (pintype "passive"))
      (node (ref "R9") (pin "1") (pinfunction "1_1") (pintype "passive"))
      (node (ref "U4") (pin "8") (pinfunction "O_8") (pintype "output"))
    )
    (net (code "73") (name "Net-(U4D-I0)") (class "Default")
      (node (ref "U4") (pin "12") (pinfunction "I0_12") (pintype "input"))
      (node (ref "U7") (pin "12") (pinfunction "Y0_12") (pintype "output"))
    )
    (net (code "74") (name "Net-(U5A-CLK)") (class "Default")
      (node (ref "C12") (pin "2") (pinfunction "2_2") (pintype "passive"))
      (node (ref "R21") (pin "1") (pinfunction "1_1") (pintype "passive"))
      (node (ref "U5") (pin "11") (pinfunction "CLK_11") (pintype "input"))
      (node (ref "U6") (pin "10") (pinfunction "O_10") (pintype "open_collector"))
    )
    (net (code "75") (name "Net-(U6A-I)") (class "Default")
      (node (ref "U6") (pin "1") (pinfunction "I_1") (pintype "input"))
      (node (ref "U7") (pin "6") (pinfunction "Y2_6") (pintype "output"))
    )
    (net (code "76") (name "Net-(U6B-I)") (class "Default")
      (node (ref "U6") (pin "3") (pinfunction "I_3") (pintype "input"))
      (node (ref "U7") (pin "5") (pinfunction "Y1_5") (pintype "output"))
    )
    (net (code "77") (name "Net-(U6C-I)") (class "Default")
      (node (ref "U6") (pin "5") (pinfunction "I_5") (pintype "input"))
      (node (ref "U7") (pin "4") (pinfunction "Y0_4") (pintype "output"))
    )
    (net (code "78") (name "Net-(U6D-I)") (class "Default")
      (node (ref "R4") (pin "1") (pinfunction "1_1") (pintype "passive"))
      (node (ref "U6") (pin "9") (pinfunction "I_9") (pintype "input"))
      (node (ref "U9") (pin "3") (pinfunction "O_3") (pintype "output"))
    )
    (net (code "79") (name "Net-(U7A-Y3)") (class "Default")
      (node (ref "D11") (pin "A") (pinfunction "A_A") (pintype "passive"))
      (node (ref "R7") (pin "1") (pinfunction "1_1") (pintype "passive"))
      (node (ref "U7") (pin "7") (pinfunction "Y3_7") (pintype "output"))
    )
    (net (code "80") (name "Net-(U7B-~{G})") (class "Default")
      (node (ref "R3") (pin "1") (pinfunction "1_1") (pintype "passive"))
      (node (ref "U7") (pin "15") (pinfunction "~{G}_15") (pintype "input"))
      (node (ref "U9") (pin "11") (pinfunction "O_11") (pintype "output"))
    )
    (net (code "81") (name "Net-(U8A-Q0)") (class "Default")
      (node (ref "R13") (pin "2") (pinfunction "2_2") (pintype "passive"))
      (node (ref "U8") (pin "2") (pinfunction "Q0_2") (pintype "tri_state"))
    )
    (net (code "82") (name "Net-(U8A-Q1)") (class "Default")
      (node (ref "R14") (pin "2") (pinfunction "2_2") (pintype "passive"))
      (node (ref "U8") (pin "5") (pinfunction "Q1_5") (pintype "tri_state"))
    )
    (net (code "83") (name "Net-(U8A-Q4)") (class "Default")
      (node (ref "R15") (pin "1") (pinfunction "1_1") (pintype "passive"))
      (node (ref "U8") (pin "12") (pinfunction "Q4_12") (pintype "tri_state"))
    )
    (net (code "84") (name "Net-(U8A-Q5)") (class "Default")
      (node (ref "U8") (pin "15") (pinfunction "Q5_15") (pintype "tri_state"))
      (node (ref "U9") (pin "4") (pinfunction "I0_4") (pintype "input"))
    )
    (net (code "85") (name "Net-(U10A-CLK)") (class "Default")
      (node (ref "C15") (pin "1") (pinfunction "1_1") (pintype "passive"))
      (node (ref "U10") (pin "11") (pinfunction "CLK_11") (pintype "input"))
      (node (ref "U6") (pin "11") (pinfunction "I_11") (pintype "input"))
      (node (ref "U9") (pin "8") (pinfunction "O_8") (pintype "output"))
    )
    (net (code "86") (name "Net-(U10A-Q3)") (class "Default")
      (node (ref "U10") (pin "9") (pinfunction "Q3_9") (pintype "tri_state"))
      (node (ref "U4") (pin "1") (pinfunction "I0_1") (pintype "input"))
    )
    (net (code "87") (name "Net-(U10A-Q4)") (class "Default")
      (node (ref "D13") (pin "A") (pinfunction "A_A") (pintype "passive"))
      (node (ref "R10") (pin "1") (pinfunction "1_1") (pintype "passive"))
      (node (ref "U10") (pin "12") (pinfunction "Q4_12") (pintype "tri_state"))
    )
    (net (code "88") (name "unconnected-(DRL1-PadP$1)") (class "Default")
      (node (ref "DRL1") (pin "P$1") (pinfunction "P$1_P$1") (pintype "passive"))
    )
    (net (code "89") (name "unconnected-(DRL2-PadP$1)") (class "Default")
      (node (ref "DRL2") (pin "P$1") (pinfunction "P$1_P$1") (pintype "passive"))
    )
    (net (code "90") (name "unconnected-(DRL3-PadP$1)") (class "Default")
      (node (ref "DRL3") (pin "P$1") (pinfunction "P$1_P$1") (pintype "passive"))
    )
    (net (code "91") (name "unconnected-(DRL4-PadP$1)") (class "Default")
      (node (ref "DRL4") (pin "P$1") (pinfunction "P$1_P$1") (pintype "passive"))
    )
    (net (code "92") (name "unconnected-(DRL5-PadP$1)") (class "Default")
      (node (ref "DRL5") (pin "P$1") (pinfunction "P$1_P$1") (pintype "passive"))
    )
    (net (code "93") (name "unconnected-(J1-CNT1-Pad4)") (class "Default")
      (node (ref "J1") (pin "4") (pinfunction "CNT1_4") (pintype "input"))
    )
    (net (code "94") (name "unconnected-(J1-CNT2-Pad6)") (class "Default")
      (node (ref "J1") (pin "6") (pinfunction "CNT2_6") (pintype "input"))
    )
    (net (code "95") (name "unconnected-(J1-~{FLAG2}-PadB)") (class "Default")
      (node (ref "J1") (pin "B") (pinfunction "~{FLAG2}_B") (pintype "input"))
    )
    (net (code "96") (name "unconnected-(J1-~{PC2}-Pad8)") (class "Default")
      (node (ref "J1") (pin "8") (pinfunction "~{PC2}_8") (pintype "bidirectional"))
    )
    (net (code "97") (name "unconnected-(J1-~{RESET}-Pad3)") (class "Default")
      (node (ref "J1") (pin "3") (pinfunction "~{RESET}_3") (pintype "bidirectional"))
    )
    (net (code "98") (name "unconnected-(JP1-Pad3)") (class "Default")
      (node (ref "JP1") (pin "3") (pinfunction "3_3") (pintype "bidirectional"))
    )
    (net (code "99") (name "unconnected-(U1-VREF-Pad6)") (class "Default")
      (node (ref "U1") (pin "6") (pinfunction "VREF_6") (pintype "output"))
    )
    (net (code "100") (name "unconnected-(U1-VZ-Pad9)") (class "Default")
      (node (ref "U1") (pin "9") (pinfunction "VZ_9") (pintype "passive"))
    )
    (net (code "101") (name "unconnected-(U2-VREF-Pad6)") (class "Default")
      (node (ref "U2") (pin "6") (pinfunction "VREF_6") (pintype "output"))
    )
    (net (code "102") (name "unconnected-(U2-VZ-Pad9)") (class "Default")
      (node (ref "U2") (pin "9") (pinfunction "VZ_9") (pintype "passive"))
    )
    (net (code "103") (name "unconnected-(U7B-Y3-Pad9)") (class "Default")
      (node (ref "U7") (pin "9") (pinfunction "Y3_9") (pintype "output"))
    )
  )
)
